# mkrd-002.net
KiCad netlist of a schematic drawn in EAGLE
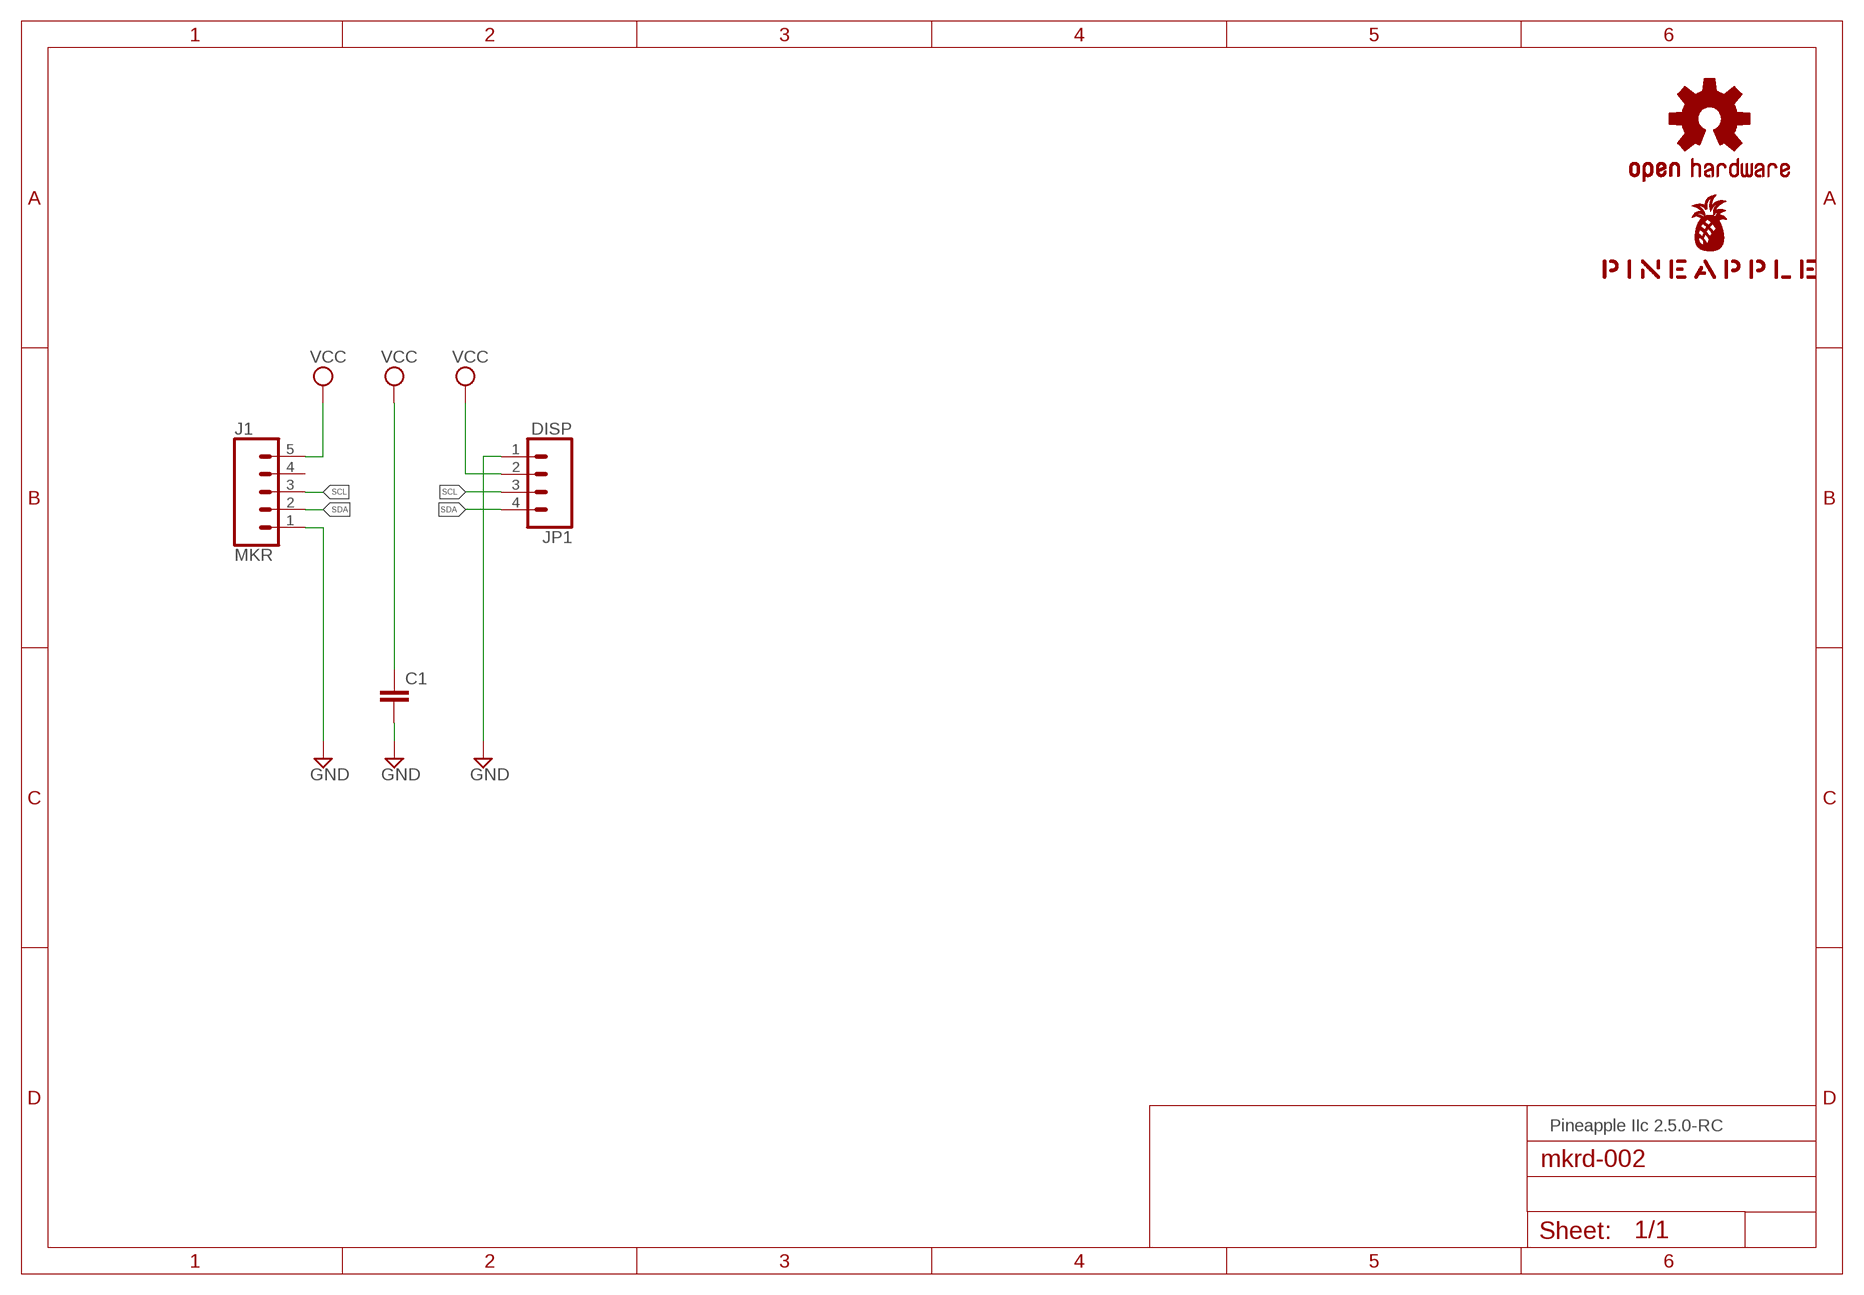
[diagram p0: schematic, sheet 1]

(export (version "E")
  (design (tool "Eeschema 10.0.6"))
  (components
    (comp (ref "C1")
      (value "C-EU025-024X044")
      (footprint "eagle-import:C025-024X044")
      (libsource (lib "eagle-import") (part "C-EU025-024X044"))
    )
    (comp (ref "J1")
      (value "MKR")
      (footprint "eagle-import:JST-5-PTH")
      (libsource (lib "eagle-import") (part "CONN_05JST"))
    )
    (comp (ref "JP1")
      (value "DISP")
      (footprint "eagle-import:1X04")
      (libsource (lib "eagle-import") (part "CONN_04"))
    )
    (comp (ref "LOGO1")
      (value "OSHW-LOGOS-COPPER")
      (footprint "eagle-import:OSHW-LOGO-S_COPPER")
      (libsource (lib "eagle-import") (part "OSHW-LOGOS-COPPER"))
    )
    (comp (ref "U$1")
      (value "PINEAPPLE450_SILK")
      (footprint "eagle-import:PINEAPPLE450_SILK")
      (libsource (lib "eagle-import") (part "PINEAPPLE450_SILK"))
    )
  )
  (nets
    (net (code "1") (name "GND") (class "Default")
      (node (ref "C1") (pin "2") (pinfunction "2_2") (pintype "passive"))
      (node (ref "J1") (pin "1") (pinfunction "1_1") (pintype "passive"))
      (node (ref "JP1") (pin "1") (pinfunction "1_1") (pintype "passive"))
    )
    (net (code "2") (name "SCL") (class "Default")
      (node (ref "J1") (pin "3") (pinfunction "3_3") (pintype "passive"))
      (node (ref "JP1") (pin "3") (pinfunction "3_3") (pintype "passive"))
    )
    (net (code "3") (name "SDA") (class "Default")
      (node (ref "J1") (pin "2") (pinfunction "2_2") (pintype "passive"))
      (node (ref "JP1") (pin "4") (pinfunction "4_4") (pintype "passive"))
    )
    (net (code "4") (name "VCC") (class "Default")
      (node (ref "C1") (pin "1") (pinfunction "1_1") (pintype "passive"))
      (node (ref "J1") (pin "5") (pinfunction "5_5") (pintype "passive"))
      (node (ref "JP1") (pin "2") (pinfunction "2_2") (pintype "passive"))
    )
    (net (code "5") (name "unconnected-(J1-Pad4)") (class "Default")
      (node (ref "J1") (pin "4") (pinfunction "4_4") (pintype "passive"))
    )
  )
)
